# amplifier_stage.net
KiCad netlist of a schematic drawn in Altium Designer
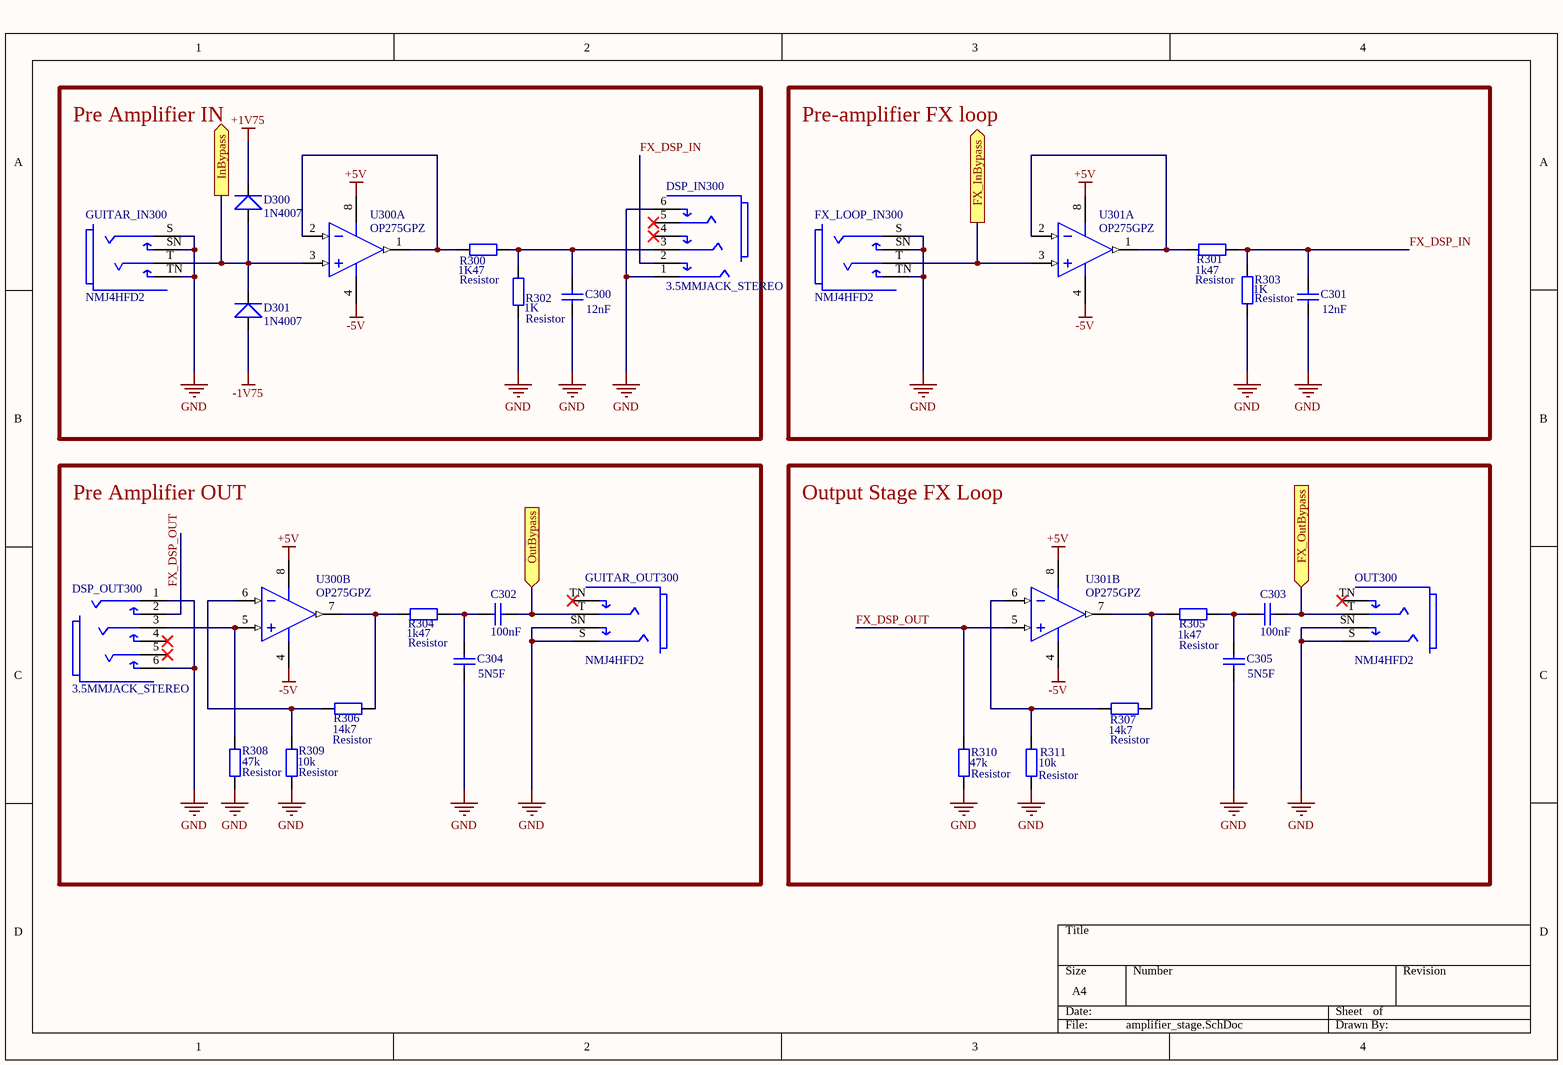
[diagram p0: amplifier_stage.SchDoc]

(export (version "E")
  (design (tool "Eeschema 10.0.6"))
  (components
    (comp (ref "C300")
      (value "12nF")
      (footprint "Cap-1")
      (fields (field (name "Comment") "Cap"))
      (libsource (lib "AAURacing") (part "Capacitor 1 space"))
    )
    (comp (ref "C301")
      (value "12nF")
      (footprint "Cap-1")
      (fields (field (name "Comment") "Cap"))
      (libsource (lib "AAURacing") (part "Capacitor 1 space"))
    )
    (comp (ref "C302")
      (value "100nF")
      (footprint "Cap-1")
      (fields (field (name "Comment") "Cap"))
      (libsource (lib "AAURacing") (part "Capacitor 1 space"))
    )
    (comp (ref "C303")
      (value "100nF")
      (footprint "Cap-1")
      (fields (field (name "Comment") "Cap"))
      (libsource (lib "AAURacing") (part "Capacitor 1 space"))
    )
    (comp (ref "C304")
      (value "5N5F")
      (footprint "Cap-1")
      (fields (field (name "Comment") "Cap"))
      (libsource (lib "AAURacing") (part "Capacitor 1 space"))
    )
    (comp (ref "C305")
      (value "5N5F")
      (footprint "Cap-1")
      (fields (field (name "Comment") "Cap"))
      (libsource (lib "AAURacing") (part "Capacitor 1 space"))
    )
    (comp (ref "D300")
      (value "1N4007")
      (footprint "1N4007")
      (libsource (lib "mit_seje_library") (part "1N4007"))
    )
    (comp (ref "D301")
      (value "1N4007")
      (footprint "1N4007")
      (libsource (lib "mit_seje_library") (part "1N4007"))
    )
    (comp (ref "DSP_IN300")
      (value "3.5MMJACK_STEREO")
      (footprint "3.5MMJACK_STEREO")
      (libsource (lib "mit_seje_library") (part "3.5MMJACK_STEREO"))
    )
    (comp (ref "DSP_OUT300")
      (value "3.5MMJACK_STEREO")
      (footprint "3.5MMJACK_STEREO")
      (libsource (lib "mit_seje_library") (part "3.5MMJACK_STEREO"))
    )
    (comp (ref "FX_LOOP_IN300")
      (value "NMJ4HFD2")
      (footprint "FP-NMJ4HFD2-MFG")
      (description "Conn 1/4\" Mono Jack F 3 POS Solder RA Thru-Hole 3 Terminal 1 Port")
      (fields
        (field (name "MANUFACTURER") "Neutrik")
        (field (name "OCTOPART") "https://octopart.com/nmj4hfd2-neutrik-758952")
      )
      (libsource (lib "Altium Content Vault") (part "8c9933f05338f077543a5425baeefa5"))
    )
    (comp (ref "GUITAR_IN300")
      (value "NMJ4HFD2")
      (footprint "FP-NMJ4HFD2-MFG")
      (description "Conn 1/4\" Mono Jack F 3 POS Solder RA Thru-Hole 3 Terminal 1 Port")
      (fields
        (field (name "MANUFACTURER") "Neutrik")
        (field (name "OCTOPART") "https://octopart.com/nmj4hfd2-neutrik-758952")
      )
      (libsource (lib "Altium Content Vault") (part "8c9933f05338f077543a5425baeefa5"))
    )
    (comp (ref "GUITAR_OUT300")
      (value "NMJ4HFD2")
      (footprint "FP-NMJ4HFD2-MFG")
      (description "Conn 1/4\" Mono Jack F 3 POS Solder RA Thru-Hole 3 Terminal 1 Port")
      (fields
        (field (name "MANUFACTURER") "Neutrik")
        (field (name "OCTOPART") "https://octopart.com/nmj4hfd2-neutrik-758952")
      )
      (libsource (lib "Altium Content Vault") (part "8c9933f05338f077543a5425baeefa5"))
    )
    (comp (ref "OUT300")
      (value "NMJ4HFD2")
      (footprint "FP-NMJ4HFD2-MFG")
      (description "Conn 1/4\" Mono Jack F 3 POS Solder RA Thru-Hole 3 Terminal 1 Port")
      (fields
        (field (name "MANUFACTURER") "Neutrik")
        (field (name "OCTOPART") "https://octopart.com/nmj4hfd2-neutrik-758952")
      )
      (libsource (lib "Altium Content Vault") (part "8c9933f05338f077543a5425baeefa5"))
    )
    (comp (ref "R300")
      (value "Resistor")
      (footprint "RES THT 9mm")
      (fields (field (name "ALTIUM_VALUE") "1K47"))
      (libsource (lib "AAURacing") (part "Resistor"))
    )
    (comp (ref "R301")
      (value "Resistor")
      (footprint "RES THT 9mm")
      (fields (field (name "ALTIUM_VALUE") "1k47"))
      (libsource (lib "AAURacing") (part "Resistor"))
    )
    (comp (ref "R302")
      (value "Resistor")
      (footprint "RES THT 9mm")
      (fields (field (name "ALTIUM_VALUE") "1K"))
      (libsource (lib "AAURacing") (part "Resistor"))
    )
    (comp (ref "R303")
      (value "Resistor")
      (footprint "RES THT 9mm")
      (fields (field (name "ALTIUM_VALUE") "1K"))
      (libsource (lib "AAURacing") (part "Resistor"))
    )
    (comp (ref "R304")
      (value "Resistor")
      (footprint "RES THT 9mm")
      (fields (field (name "ALTIUM_VALUE") "1k47"))
      (libsource (lib "AAURacing") (part "Resistor"))
    )
    (comp (ref "R305")
      (value "Resistor")
      (footprint "RES THT 9mm")
      (fields (field (name "ALTIUM_VALUE") "1k47"))
      (libsource (lib "AAURacing") (part "Resistor"))
    )
    (comp (ref "R306")
      (value "Resistor")
      (footprint "RES THT 9mm")
      (fields (field (name "ALTIUM_VALUE") "14k7"))
      (libsource (lib "AAURacing") (part "Resistor"))
    )
    (comp (ref "R307")
      (value "Resistor")
      (footprint "RES THT 9mm")
      (fields (field (name "ALTIUM_VALUE") "14k7"))
      (libsource (lib "AAURacing") (part "Resistor"))
    )
    (comp (ref "R308")
      (value "Resistor")
      (footprint "RES THT 9mm")
      (fields (field (name "ALTIUM_VALUE") "47k"))
      (libsource (lib "AAURacing") (part "Resistor"))
    )
    (comp (ref "R309")
      (value "Resistor")
      (footprint "RES THT 9mm")
      (fields (field (name "ALTIUM_VALUE") "10k"))
      (libsource (lib "AAURacing") (part "Resistor"))
    )
    (comp (ref "R310")
      (value "Resistor")
      (footprint "RES THT 9mm")
      (fields (field (name "ALTIUM_VALUE") "47k"))
      (libsource (lib "AAURacing") (part "Resistor"))
    )
    (comp (ref "R311")
      (value "Resistor")
      (footprint "RES THT 9mm")
      (fields (field (name "ALTIUM_VALUE") "10k"))
      (libsource (lib "AAURacing") (part "Resistor"))
    )
    (comp (ref "U300")
      (value "OP275GPZ")
      (footprint "ADI-N-8")
      (fields (field (name "MANUFACTURER") "Analog Devices") (field (name "GENERIC PART NUMBER") "OP275"))
      (libsource (lib "Altium Content Vault") (part "ADI-OP29X-R-8"))
    )
    (comp (ref "U301")
      (value "OP275GPZ")
      (footprint "ADI-N-8")
      (fields (field (name "MANUFACTURER") "Analog Devices") (field (name "GENERIC PART NUMBER") "OP275"))
      (libsource (lib "Altium Content Vault") (part "ADI-OP29X-R-8"))
    )
  )
  (nets
    (net (code "1") (name "+1V75") (class "Default")
      (node (ref "D300") (pin "2") (pinfunction "2_2") (pintype "passive"))
    )
    (net (code "2") (name "+5V") (class "Default")
      (node (ref "U300") (pin "8") (pinfunction "+V_8") (pintype "power_in"))
      (node (ref "U301") (pin "8") (pinfunction "+V_8") (pintype "power_in"))
    )
    (net (code "3") (name "-1V75") (class "Default")
      (node (ref "D301") (pin "1") (pinfunction "1_1") (pintype "passive"))
    )
    (net (code "4") (name "-5V") (class "Default")
      (node (ref "U300") (pin "4") (pinfunction "-V_4") (pintype "power_in"))
      (node (ref "U301") (pin "4") (pinfunction "-V_4") (pintype "power_in"))
    )
    (net (code "5") (name "/FX_DSP_IN") (class "Default")
      (node (ref "C301") (pin "2") (pinfunction "g_2") (pintype "passive"))
      (node (ref "DSP_IN300") (pin "2") (pinfunction "SN_2") (pintype "passive"))
      (node (ref "R301") (pin "2") (pinfunction "2_2") (pintype "passive"))
      (node (ref "R303") (pin "2") (pinfunction "2_2") (pintype "passive"))
    )
    (net (code "6") (name "/FX_DSP_OUT") (class "Default")
      (node (ref "DSP_OUT300") (pin "2") (pinfunction "SN_2") (pintype "passive"))
      (node (ref "R310") (pin "2") (pinfunction "2_2") (pintype "passive"))
      (node (ref "U301") (pin "5") (pinfunction "+IN_B_5") (pintype "input"))
    )
    (net (code "7") (name "/FX_InBypass") (class "Default")
      (node (ref "FX_LOOP_IN300") (pin "T") (pinfunction "T_T") (pintype "passive"))
      (node (ref "U301") (pin "3") (pinfunction "+IN_A_3") (pintype "input"))
    )
    (net (code "8") (name "/FX_OutBypass") (class "Default")
      (node (ref "C303") (pin "1") (pinfunction "1_1") (pintype "passive"))
      (node (ref "OUT300") (pin "T") (pinfunction "T_T") (pintype "passive"))
    )
    (net (code "9") (name "/InBypass") (class "Default")
      (node (ref "D300") (pin "1") (pinfunction "1_1") (pintype "passive"))
      (node (ref "D301") (pin "2") (pinfunction "2_2") (pintype "passive"))
      (node (ref "GUITAR_IN300") (pin "T") (pinfunction "T_T") (pintype "passive"))
      (node (ref "U300") (pin "3") (pinfunction "+IN_A_3") (pintype "input"))
    )
    (net (code "10") (name "/OutBypass") (class "Default")
      (node (ref "C302") (pin "1") (pinfunction "1_1") (pintype "passive"))
      (node (ref "GUITAR_OUT300") (pin "T") (pinfunction "T_T") (pintype "passive"))
    )
    (net (code "11") (name "GND") (class "Default")
      (node (ref "C300") (pin "1") (pinfunction "1_1") (pintype "passive"))
      (node (ref "C301") (pin "1") (pinfunction "1_1") (pintype "passive"))
      (node (ref "C304") (pin "1") (pinfunction "1_1") (pintype "passive"))
      (node (ref "C305") (pin "1") (pinfunction "1_1") (pintype "passive"))
      (node (ref "DSP_IN300") (pin "1") (pinfunction "S_1") (pintype "passive"))
      (node (ref "DSP_IN300") (pin "6") (pinfunction "TN_6") (pintype "passive"))
      (node (ref "DSP_OUT300") (pin "1") (pinfunction "S_1") (pintype "passive"))
      (node (ref "DSP_OUT300") (pin "6") (pinfunction "TN_6") (pintype "passive"))
      (node (ref "FX_LOOP_IN300") (pin "S") (pinfunction "S_S") (pintype "passive"))
      (node (ref "FX_LOOP_IN300") (pin "SN") (pinfunction "SN_SN") (pintype "passive"))
      (node (ref "FX_LOOP_IN300") (pin "TN") (pinfunction "TN_TN") (pintype "passive"))
      (node (ref "GUITAR_IN300") (pin "S") (pinfunction "S_S") (pintype "passive"))
      (node (ref "GUITAR_IN300") (pin "SN") (pinfunction "SN_SN") (pintype "passive"))
      (node (ref "GUITAR_IN300") (pin "TN") (pinfunction "TN_TN") (pintype "passive"))
      (node (ref "GUITAR_OUT300") (pin "S") (pinfunction "S_S") (pintype "passive"))
      (node (ref "GUITAR_OUT300") (pin "SN") (pinfunction "SN_SN") (pintype "passive"))
      (node (ref "OUT300") (pin "S") (pinfunction "S_S") (pintype "passive"))
      (node (ref "OUT300") (pin "SN") (pinfunction "SN_SN") (pintype "passive"))
      (node (ref "R302") (pin "1") (pinfunction "1_1") (pintype "passive"))
      (node (ref "R303") (pin "1") (pinfunction "1_1") (pintype "passive"))
      (node (ref "R308") (pin "1") (pinfunction "1_1") (pintype "passive"))
      (node (ref "R309") (pin "1") (pinfunction "1_1") (pintype "passive"))
      (node (ref "R310") (pin "1") (pinfunction "1_1") (pintype "passive"))
      (node (ref "R311") (pin "1") (pinfunction "1_1") (pintype "passive"))
    )
    (net (code "12") (name "Net-(C300-g)") (class "Default")
      (node (ref "C300") (pin "2") (pinfunction "g_2") (pintype "passive"))
      (node (ref "DSP_IN300") (pin "3") (pinfunction "S_3") (pintype "passive"))
      (node (ref "R300") (pin "2") (pinfunction "2_2") (pintype "passive"))
      (node (ref "R302") (pin "2") (pinfunction "2_2") (pintype "passive"))
    )
    (net (code "13") (name "Net-(C302-g)") (class "Default")
      (node (ref "C302") (pin "2") (pinfunction "g_2") (pintype "passive"))
      (node (ref "C304") (pin "2") (pinfunction "g_2") (pintype "passive"))
      (node (ref "R304") (pin "2") (pinfunction "2_2") (pintype "passive"))
    )
    (net (code "14") (name "Net-(C303-g)") (class "Default")
      (node (ref "C303") (pin "2") (pinfunction "g_2") (pintype "passive"))
      (node (ref "C305") (pin "2") (pinfunction "g_2") (pintype "passive"))
      (node (ref "R305") (pin "2") (pinfunction "2_2") (pintype "passive"))
    )
    (net (code "15") (name "Net-(U300A--IN_A)") (class "Default")
      (node (ref "R300") (pin "1") (pinfunction "1_1") (pintype "passive"))
      (node (ref "U300") (pin "1") (pinfunction "OUT_A_1") (pintype "output"))
      (node (ref "U300") (pin "2") (pinfunction "-IN_A_2") (pintype "input"))
    )
    (net (code "16") (name "Net-(U300B-+IN_B)") (class "Default")
      (node (ref "DSP_OUT300") (pin "3") (pinfunction "S_3") (pintype "passive"))
      (node (ref "R308") (pin "2") (pinfunction "2_2") (pintype "passive"))
      (node (ref "U300") (pin "5") (pinfunction "+IN_B_5") (pintype "input"))
    )
    (net (code "17") (name "Net-(U300B--IN_B)") (class "Default")
      (node (ref "R306") (pin "1") (pinfunction "1_1") (pintype "passive"))
      (node (ref "R309") (pin "2") (pinfunction "2_2") (pintype "passive"))
      (node (ref "U300") (pin "6") (pinfunction "-IN_B_6") (pintype "input"))
    )
    (net (code "18") (name "Net-(U300B-OUT_B)") (class "Default")
      (node (ref "R304") (pin "1") (pinfunction "1_1") (pintype "passive"))
      (node (ref "R306") (pin "2") (pinfunction "2_2") (pintype "passive"))
      (node (ref "U300") (pin "7") (pinfunction "OUT_B_7") (pintype "output"))
    )
    (net (code "19") (name "Net-(U301A--IN_A)") (class "Default")
      (node (ref "R301") (pin "1") (pinfunction "1_1") (pintype "passive"))
      (node (ref "U301") (pin "1") (pinfunction "OUT_A_1") (pintype "output"))
      (node (ref "U301") (pin "2") (pinfunction "-IN_A_2") (pintype "input"))
    )
    (net (code "20") (name "Net-(U301B--IN_B)") (class "Default")
      (node (ref "R307") (pin "1") (pinfunction "1_1") (pintype "passive"))
      (node (ref "R311") (pin "2") (pinfunction "2_2") (pintype "passive"))
      (node (ref "U301") (pin "6") (pinfunction "-IN_B_6") (pintype "input"))
    )
    (net (code "21") (name "Net-(U301B-OUT_B)") (class "Default")
      (node (ref "R305") (pin "1") (pinfunction "1_1") (pintype "passive"))
      (node (ref "R307") (pin "2") (pinfunction "2_2") (pintype "passive"))
      (node (ref "U301") (pin "7") (pinfunction "OUT_B_7") (pintype "output"))
    )
    (net (code "22") (name "unconnected-(DSP_IN300-SN-Pad4)") (class "Default")
      (node (ref "DSP_IN300") (pin "4") (pinfunction "SN_4") (pintype "passive+no_connect"))
    )
    (net (code "23") (name "unconnected-(DSP_IN300-T-Pad5)") (class "Default")
      (node (ref "DSP_IN300") (pin "5") (pinfunction "T_5") (pintype "passive+no_connect"))
    )
    (net (code "24") (name "unconnected-(DSP_OUT300-SN-Pad4)") (class "Default")
      (node (ref "DSP_OUT300") (pin "4") (pinfunction "SN_4") (pintype "passive+no_connect"))
    )
    (net (code "25") (name "unconnected-(DSP_OUT300-T-Pad5)") (class "Default")
      (node (ref "DSP_OUT300") (pin "5") (pinfunction "T_5") (pintype "passive+no_connect"))
    )
    (net (code "26") (name "unconnected-(GUITAR_OUT300-PadTN)") (class "Default")
      (node (ref "GUITAR_OUT300") (pin "TN") (pinfunction "TN_TN") (pintype "passive+no_connect"))
    )
    (net (code "27") (name "unconnected-(OUT300-PadTN)") (class "Default")
      (node (ref "OUT300") (pin "TN") (pinfunction "TN_TN") (pintype "passive+no_connect"))
    )
  )
)
